# ecu_sch.net
KiCad netlist of a schematic drawn in EAGLE
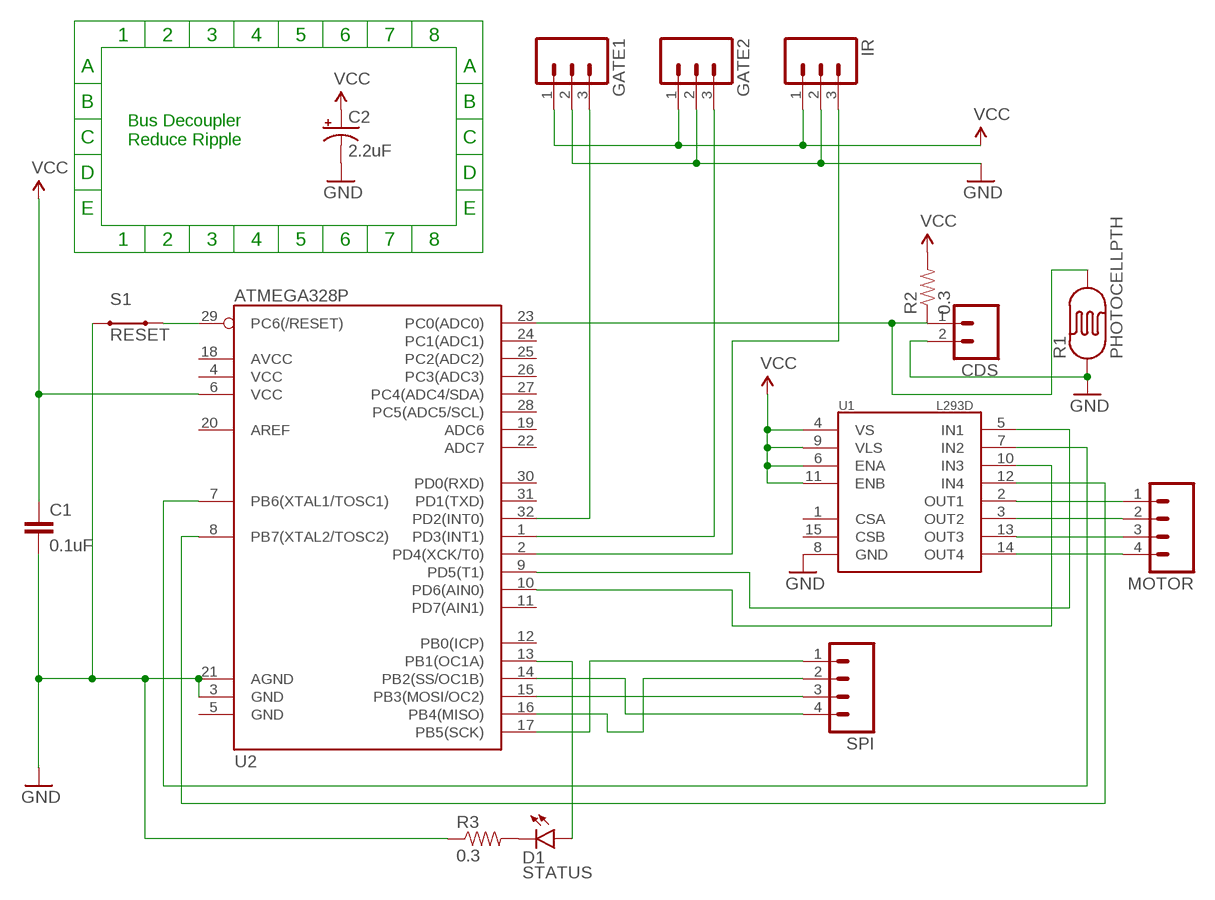
[diagram p0: schematic, sheet 1]

(export (version "E")
  (design (tool "Eeschema 10.0.6"))
  (components
    (comp (ref "C1")
      (value "0.1uF")
      (footprint "eagle-import:0603-CAP")
      (libsource (lib "eagle-import") (part "0.1UF-25V(+80/-20%)(0603)"))
    )
    (comp (ref "C2")
      (value "2.2uF")
      (footprint "eagle-import:EIA3528")
      (libsource (lib "eagle-import") (part "47UF-10V-10%(TANT)"))
    )
    (comp (ref "CDS")
      (value "M02JST-PTH-2")
      (footprint "eagle-import:JST-2-PTH")
      (libsource (lib "eagle-import") (part "M02JST-PTH-2"))
    )
    (comp (ref "D1")
      (value "STATUS")
      (footprint "eagle-import:LED-1206")
      (libsource (lib "eagle-import") (part "LED-WHITE"))
    )
    (comp (ref "GATE1")
      (value "M03JST-PTH")
      (footprint "eagle-import:JST-3-PTH")
      (libsource (lib "eagle-import") (part "M03JST-PTH"))
    )
    (comp (ref "GATE2")
      (value "M03JST-PTH")
      (footprint "eagle-import:JST-3-PTH")
      (libsource (lib "eagle-import") (part "M03JST-PTH"))
    )
    (comp (ref "IR")
      (value "M03JST-PTH")
      (footprint "eagle-import:JST-3-PTH")
      (libsource (lib "eagle-import") (part "M03JST-PTH"))
    )
    (comp (ref "MOTOR")
      (value "M04JST-PTH")
      (footprint "eagle-import:JST-4-PTH")
      (libsource (lib "eagle-import") (part "M04JST-PTH"))
    )
    (comp (ref "R1")
      (value "PHOTOCELLPTH")
      (footprint "eagle-import:PHOTOCELL")
      (libsource (lib "eagle-import") (part "PHOTOCELLPTH"))
    )
    (comp (ref "R2")
      (value "0.3")
      (footprint "eagle-import:0805")
      (libsource (lib "eagle-import") (part "0.3OHM-1/8W-1%(0805)"))
    )
    (comp (ref "R3")
      (value "0.3")
      (footprint "eagle-import:0805")
      (libsource (lib "eagle-import") (part "0.3OHM-1/8W-1%(0805)"))
    )
    (comp (ref "S1")
      (value "RESET")
      (footprint "eagle-import:TACTILE-PTH-12MM")
      (libsource (lib "eagle-import") (part "SWITCH-MOMENTARY-2-CLOSED"))
    )
    (comp (ref "SPI")
      (value "M04JST-PTH")
      (footprint "eagle-import:JST-4-PTH")
      (libsource (lib "eagle-import") (part "M04JST-PTH"))
    )
    (comp (ref "U1")
      (value "L293D")
      (footprint "eagle-import:MULTIWATT15")
      (libsource (lib "eagle-import") (part "L298"))
    )
    (comp (ref "U2")
      (value "ATMEGA328P")
      (footprint "eagle-import:TQFP32-08")
      (libsource (lib "eagle-import") (part "ATMEGA328_SMT"))
    )
  )
  (nets
    (net (code "1") (name "GND") (class "Default")
      (node (ref "C1") (pin "2") (pinfunction "2_2") (pintype "passive"))
      (node (ref "C2") (pin "C") (pinfunction "-_C") (pintype "passive"))
      (node (ref "CDS") (pin "2") (pinfunction "2_2") (pintype "passive"))
      (node (ref "GATE1") (pin "2") (pinfunction "2_2") (pintype "passive"))
      (node (ref "GATE2") (pin "2") (pinfunction "2_2") (pintype "passive"))
      (node (ref "IR") (pin "2") (pinfunction "2_2") (pintype "passive"))
      (node (ref "R1") (pin "1") (pinfunction "P$1_1") (pintype "bidirectional"))
      (node (ref "R3") (pin "1") (pinfunction "1_1") (pintype "passive"))
      (node (ref "S1") (pin "1") (pinfunction "1_1") (pintype "passive"))
      (node (ref "U1") (pin "8") (pinfunction "GND_8") (pintype "bidirectional"))
      (node (ref "U2") (pin "21") (pinfunction "AGND_21") (pintype "bidirectional"))
      (node (ref "U2") (pin "3") (pinfunction "GND_3") (pintype "bidirectional"))
    )
    (net (code "2") (name "Net-(D1-PadC)") (class "Default")
      (node (ref "D1") (pin "C") (pinfunction "C_C") (pintype "passive"))
      (node (ref "R3") (pin "2") (pinfunction "2_2") (pintype "passive"))
    )
    (net (code "3") (name "Net-(R1-P$2)") (class "Default")
      (node (ref "CDS") (pin "1") (pinfunction "1_1") (pintype "passive"))
      (node (ref "R1") (pin "2") (pinfunction "P$2_2") (pintype "bidirectional"))
      (node (ref "R2") (pin "1") (pinfunction "1_1") (pintype "passive"))
      (node (ref "U2") (pin "23") (pinfunction "PC0(ADC0)_23") (pintype "bidirectional"))
    )
    (net (code "4") (name "Net-(S1-2)") (class "Default")
      (node (ref "S1") (pin "3") (pinfunction "2_3") (pintype "passive"))
      (node (ref "U2") (pin "29") (pinfunction "PC6(/RESET)_29") (pintype "bidirectional"))
    )
    (net (code "5") (name "Net-(U1-IN1)") (class "Default")
      (node (ref "U1") (pin "5") (pinfunction "IN1_5") (pintype "bidirectional"))
      (node (ref "U2") (pin "9") (pinfunction "PD5(T1)_9") (pintype "bidirectional"))
    )
    (net (code "6") (name "Net-(U1-IN2)") (class "Default")
      (node (ref "U1") (pin "7") (pinfunction "IN2_7") (pintype "bidirectional"))
      (node (ref "U2") (pin "7") (pinfunction "PB6(XTAL1/TOSC1)_7") (pintype "bidirectional"))
    )
    (net (code "7") (name "Net-(U1-IN3)") (class "Default")
      (node (ref "U1") (pin "10") (pinfunction "IN3_10") (pintype "bidirectional"))
      (node (ref "U2") (pin "10") (pinfunction "PD6(AIN0)_10") (pintype "bidirectional"))
    )
    (net (code "8") (name "Net-(U1-IN4)") (class "Default")
      (node (ref "U1") (pin "12") (pinfunction "IN4_12") (pintype "bidirectional"))
      (node (ref "U2") (pin "8") (pinfunction "PB7(XTAL2/TOSC2)_8") (pintype "bidirectional"))
    )
    (net (code "9") (name "Net-(U1-OUT1)") (class "Default")
      (node (ref "MOTOR") (pin "1") (pinfunction "1_1") (pintype "passive"))
      (node (ref "U1") (pin "2") (pinfunction "OUT1_2") (pintype "bidirectional"))
    )
    (net (code "10") (name "Net-(U1-OUT2)") (class "Default")
      (node (ref "MOTOR") (pin "2") (pinfunction "2_2") (pintype "passive"))
      (node (ref "U1") (pin "3") (pinfunction "OUT2_3") (pintype "bidirectional"))
    )
    (net (code "11") (name "Net-(U1-OUT3)") (class "Default")
      (node (ref "MOTOR") (pin "3") (pinfunction "3_3") (pintype "passive"))
      (node (ref "U1") (pin "13") (pinfunction "OUT3_13") (pintype "bidirectional"))
    )
    (net (code "12") (name "Net-(U1-OUT4)") (class "Default")
      (node (ref "MOTOR") (pin "4") (pinfunction "4_4") (pintype "passive"))
      (node (ref "U1") (pin "14") (pinfunction "OUT4_14") (pintype "bidirectional"))
    )
    (net (code "13") (name "Net-(U2-PB1(OC1A))") (class "Default")
      (node (ref "D1") (pin "A") (pinfunction "A_A") (pintype "passive"))
      (node (ref "U2") (pin "13") (pinfunction "PB1(OC1A)_13") (pintype "bidirectional"))
    )
    (net (code "14") (name "Net-(U2-PB2(SS{slash}OC1B))") (class "Default")
      (node (ref "SPI") (pin "4") (pinfunction "4_4") (pintype "passive"))
      (node (ref "U2") (pin "14") (pinfunction "PB2(SS/OC1B)_14") (pintype "bidirectional"))
    )
    (net (code "15") (name "Net-(U2-PB3(MOSI{slash}OC2))") (class "Default")
      (node (ref "SPI") (pin "3") (pinfunction "3_3") (pintype "passive"))
      (node (ref "U2") (pin "15") (pinfunction "PB3(MOSI/OC2)_15") (pintype "bidirectional"))
    )
    (net (code "16") (name "Net-(U2-PB4(MISO))") (class "Default")
      (node (ref "SPI") (pin "2") (pinfunction "2_2") (pintype "passive"))
      (node (ref "U2") (pin "16") (pinfunction "PB4(MISO)_16") (pintype "bidirectional"))
    )
    (net (code "17") (name "Net-(U2-PB5(SCK))") (class "Default")
      (node (ref "SPI") (pin "1") (pinfunction "1_1") (pintype "passive"))
      (node (ref "U2") (pin "17") (pinfunction "PB5(SCK)_17") (pintype "bidirectional"))
    )
    (net (code "18") (name "Net-(U2-PD2(INT0))") (class "Default")
      (node (ref "GATE1") (pin "3") (pinfunction "3_3") (pintype "passive"))
      (node (ref "U2") (pin "32") (pinfunction "PD2(INT0)_32") (pintype "bidirectional"))
    )
    (net (code "19") (name "Net-(U2-PD3(INT1))") (class "Default")
      (node (ref "GATE2") (pin "3") (pinfunction "3_3") (pintype "passive"))
      (node (ref "U2") (pin "1") (pinfunction "PD3(INT1)_1") (pintype "bidirectional"))
    )
    (net (code "20") (name "Net-(U2-PD4(XCK{slash}T0))") (class "Default")
      (node (ref "IR") (pin "3") (pinfunction "3_3") (pintype "passive"))
      (node (ref "U2") (pin "2") (pinfunction "PD4(XCK/T0)_2") (pintype "bidirectional"))
    )
    (net (code "21") (name "VCC") (class "Default")
      (node (ref "C1") (pin "1") (pinfunction "1_1") (pintype "passive"))
      (node (ref "C2") (pin "A") (pinfunction "+_A") (pintype "passive"))
      (node (ref "GATE1") (pin "1") (pinfunction "1_1") (pintype "passive"))
      (node (ref "GATE2") (pin "1") (pinfunction "1_1") (pintype "passive"))
      (node (ref "IR") (pin "1") (pinfunction "1_1") (pintype "passive"))
      (node (ref "R2") (pin "2") (pinfunction "2_2") (pintype "passive"))
      (node (ref "U1") (pin "11") (pinfunction "ENB_11") (pintype "bidirectional"))
      (node (ref "U1") (pin "4") (pinfunction "VS_4") (pintype "bidirectional"))
      (node (ref "U1") (pin "6") (pinfunction "ENA_6") (pintype "bidirectional"))
      (node (ref "U1") (pin "9") (pinfunction "VLS_9") (pintype "bidirectional"))
      (node (ref "U2") (pin "6") (pinfunction "VCC_6") (pintype "bidirectional"))
    )
    (net (code "22") (name "unconnected-(U1-CSA-Pad1)") (class "Default")
      (node (ref "U1") (pin "1") (pinfunction "CSA_1") (pintype "bidirectional"))
    )
    (net (code "23") (name "unconnected-(U1-CSB-Pad15)") (class "Default")
      (node (ref "U1") (pin "15") (pinfunction "CSB_15") (pintype "bidirectional"))
    )
    (net (code "24") (name "unconnected-(U2-ADC6-Pad19)") (class "Default")
      (node (ref "U2") (pin "19") (pinfunction "ADC6_19") (pintype "bidirectional"))
    )
    (net (code "25") (name "unconnected-(U2-ADC7-Pad22)") (class "Default")
      (node (ref "U2") (pin "22") (pinfunction "ADC7_22") (pintype "bidirectional"))
    )
    (net (code "26") (name "unconnected-(U2-AREF-Pad20)") (class "Default")
      (node (ref "U2") (pin "20") (pinfunction "AREF_20") (pintype "bidirectional"))
    )
    (net (code "27") (name "unconnected-(U2-AVCC-Pad18)") (class "Default")
      (node (ref "U2") (pin "18") (pinfunction "AVCC_18") (pintype "bidirectional"))
    )
    (net (code "28") (name "unconnected-(U2-GND-Pad5)") (class "Default")
      (node (ref "U2") (pin "5") (pinfunction "GND_5") (pintype "bidirectional"))
    )
    (net (code "29") (name "unconnected-(U2-PB0(ICP)-Pad12)") (class "Default")
      (node (ref "U2") (pin "12") (pinfunction "PB0(ICP)_12") (pintype "bidirectional"))
    )
    (net (code "30") (name "unconnected-(U2-PC1(ADC1)-Pad24)") (class "Default")
      (node (ref "U2") (pin "24") (pinfunction "PC1(ADC1)_24") (pintype "bidirectional"))
    )
    (net (code "31") (name "unconnected-(U2-PC2(ADC2)-Pad25)") (class "Default")
      (node (ref "U2") (pin "25") (pinfunction "PC2(ADC2)_25") (pintype "bidirectional"))
    )
    (net (code "32") (name "unconnected-(U2-PC3(ADC3)-Pad26)") (class "Default")
      (node (ref "U2") (pin "26") (pinfunction "PC3(ADC3)_26") (pintype "bidirectional"))
    )
    (net (code "33") (name "unconnected-(U2-PC4(ADC4{slash}SDA)-Pad27)") (class "Default")
      (node (ref "U2") (pin "27") (pinfunction "PC4(ADC4/SDA)_27") (pintype "bidirectional"))
    )
    (net (code "34") (name "unconnected-(U2-PC5(ADC5{slash}SCL)-Pad28)") (class "Default")
      (node (ref "U2") (pin "28") (pinfunction "PC5(ADC5/SCL)_28") (pintype "bidirectional"))
    )
    (net (code "35") (name "unconnected-(U2-PD0(RXD)-Pad30)") (class "Default")
      (node (ref "U2") (pin "30") (pinfunction "PD0(RXD)_30") (pintype "bidirectional"))
    )
    (net (code "36") (name "unconnected-(U2-PD1(TXD)-Pad31)") (class "Default")
      (node (ref "U2") (pin "31") (pinfunction "PD1(TXD)_31") (pintype "bidirectional"))
    )
    (net (code "37") (name "unconnected-(U2-PD7(AIN1)-Pad11)") (class "Default")
      (node (ref "U2") (pin "11") (pinfunction "PD7(AIN1)_11") (pintype "bidirectional"))
    )
    (net (code "38") (name "unconnected-(U2-VCC-Pad4)") (class "Default")
      (node (ref "U2") (pin "4") (pinfunction "VCC_4") (pintype "bidirectional"))
    )
  )
)
